# 2024-4T-MNT-3.net
KiCad netlist of a schematic drawn in EasyEDA Pro
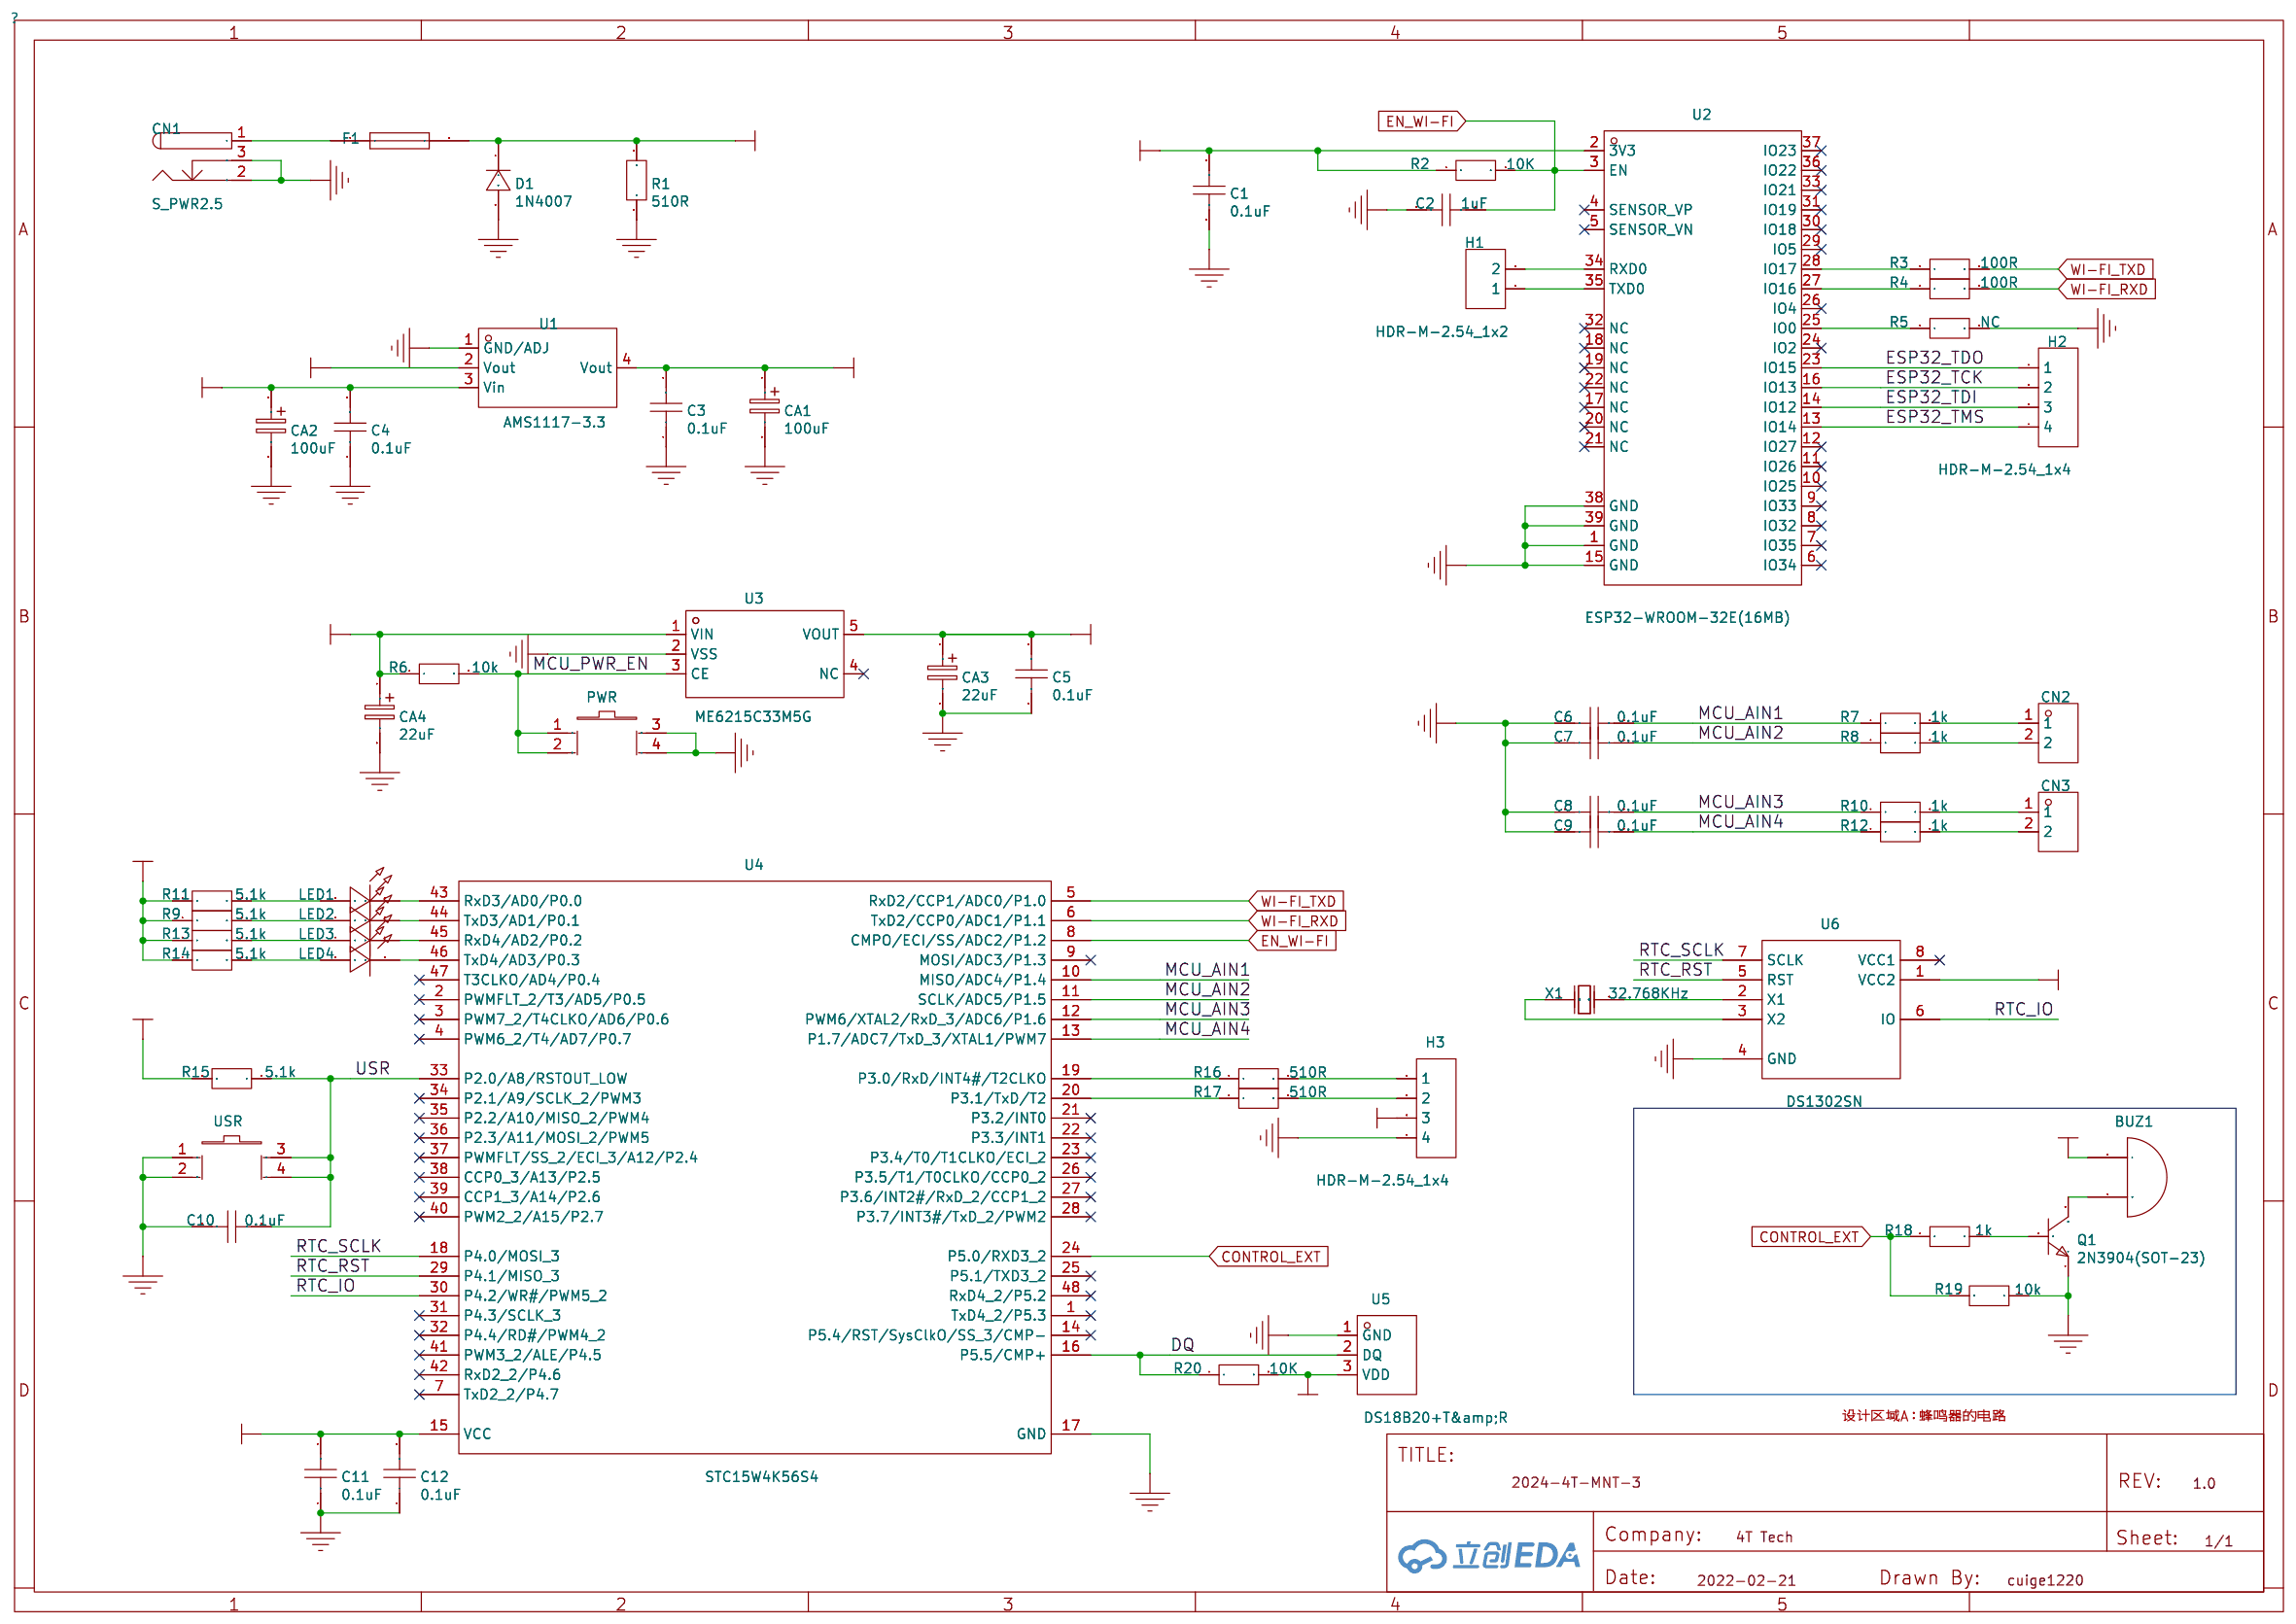
[diagram p0: schematic sheet]

(export (version "E")
  (design (tool "Eeschema 10.0.6"))
  (components
    (comp (ref "BUZ1") (value "BUZ1") (libsource (lib "easyedapro") (part "BUZ1")))
    (comp (ref "C1") (value "0.1uF") (libsource (lib "easyedapro") (part "0.1uF")))
    (comp (ref "C2") (value "1uF") (libsource (lib "easyedapro") (part "1uF")))
    (comp (ref "C3") (value "0.1uF") (libsource (lib "easyedapro") (part "0.1uF")))
    (comp (ref "C4") (value "0.1uF") (libsource (lib "easyedapro") (part "0.1uF")))
    (comp (ref "C5") (value "0.1uF") (libsource (lib "easyedapro") (part "0.1uF")))
    (comp (ref "C6") (value "0.1uF") (libsource (lib "easyedapro") (part "0.1uF")))
    (comp (ref "C7") (value "0.1uF") (libsource (lib "easyedapro") (part "0.1uF")))
    (comp (ref "C8") (value "0.1uF") (libsource (lib "easyedapro") (part "0.1uF")))
    (comp (ref "C9") (value "0.1uF") (libsource (lib "easyedapro") (part "0.1uF")))
    (comp (ref "C10") (value "0.1uF") (libsource (lib "easyedapro") (part "0.1uF")))
    (comp (ref "C11") (value "0.1uF") (libsource (lib "easyedapro") (part "0.1uF")))
    (comp (ref "C12") (value "0.1uF") (libsource (lib "easyedapro") (part "0.1uF")))
    (comp (ref "CA1") (value "100uF") (libsource (lib "easyedapro") (part "100uF")))
    (comp (ref "CA2") (value "100uF") (libsource (lib "easyedapro") (part "100uF")))
    (comp (ref "CA3") (value "22uF") (libsource (lib "easyedapro") (part "22uF")))
    (comp (ref "CA4") (value "22uF") (libsource (lib "easyedapro") (part "22uF")))
    (comp (ref "CN1") (value "S_PWR2.5") (libsource (lib "easyedapro") (part "S_PWR2.5")))
    (comp (ref "CN2")
      (value "DB128L-5.08-2P")
      (fields (field (name "Manufacturer") "DIBO"))
      (libsource (lib "easyedapro") (part "DB128L-5.08-2P"))
    )
    (comp (ref "CN3")
      (value "DB128L-5.08-2P")
      (fields (field (name "Manufacturer") "DIBO"))
      (libsource (lib "easyedapro") (part "DB128L-5.08-2P"))
    )
    (comp (ref "D1")
      (value "1N4007")
      (fields (field (name "Manufacturer") "SEMTECH"))
      (libsource (lib "easyedapro") (part "1N4007"))
    )
    (comp (ref "F1")
      (value "ASMD1210-075")
      (fields (field (name "Publisher") "Altium Limited"))
      (libsource (lib "easyedapro") (part "ASMD1210-075"))
    )
    (comp (ref "H1") (value "HDR-M-2.54_1x2") (libsource (lib "easyedapro") (part "HDR-M-2.54_1x2")))
    (comp (ref "H2") (value "HDR-M-2.54_1x4") (libsource (lib "easyedapro") (part "HDR-M-2.54_1x4")))
    (comp (ref "H3") (value "HDR-M-2.54_1x4") (libsource (lib "easyedapro") (part "HDR-M-2.54_1x4")))
    (comp (ref "LED1")
      (value "LED-TH-3mm_R")
      (fields
        (field (name "Manufacturer Part") "204-10SDRD/S530-A3-L")
        (field (name "Manufacturer") "EVERLIGHT(台湾亿光)")
      )
      (libsource (lib "easyedapro") (part "LED-TH-3mm_R"))
    )
    (comp (ref "LED2")
      (value "LED-TH-3mm_R")
      (fields
        (field (name "Manufacturer Part") "204-10SDRD/S530-A3-L")
        (field (name "Manufacturer") "EVERLIGHT(台湾亿光)")
      )
      (libsource (lib "easyedapro") (part "LED-TH-3mm_R"))
    )
    (comp (ref "LED3")
      (value "LED-TH-3mm_R")
      (fields
        (field (name "Manufacturer Part") "204-10SDRD/S530-A3-L")
        (field (name "Manufacturer") "EVERLIGHT(台湾亿光)")
      )
      (libsource (lib "easyedapro") (part "LED-TH-3mm_R"))
    )
    (comp (ref "LED4")
      (value "LED-TH-3mm_R")
      (fields
        (field (name "Manufacturer Part") "204-10SDRD/S530-A3-L")
        (field (name "Manufacturer") "EVERLIGHT(台湾亿光)")
      )
      (libsource (lib "easyedapro") (part "LED-TH-3mm_R"))
    )
    (comp (ref "PWR")
      (value "6x6x6Plastic head")
      (fields (field (name "Manufacturer") "ReliaPro"))
      (libsource (lib "easyedapro") (part "6x6x6Plastic head"))
    )
    (comp (ref "Q1")
      (value "2N3904(SOT-23)")
      (fields (field (name "Manufacturer Part") "2n3904S-RTK/PS") (field (name "Manufacturer") "KEC"))
      (libsource (lib "easyedapro") (part "2N3904(SOT-23)"))
    )
    (comp (ref "R1") (value "510R") (libsource (lib "easyedapro") (part "510R")))
    (comp (ref "R2") (value "10K") (libsource (lib "easyedapro") (part "10k")))
    (comp (ref "R3") (value "100R") (libsource (lib "easyedapro") (part "100R")))
    (comp (ref "R4") (value "100R") (libsource (lib "easyedapro") (part "100R")))
    (comp (ref "R5") (value "NC") (libsource (lib "easyedapro") (part "NC")))
    (comp (ref "R6") (value "10k") (libsource (lib "easyedapro") (part "10k")))
    (comp (ref "R7") (value "1k") (libsource (lib "easyedapro") (part "1K")))
    (comp (ref "R8") (value "1k") (libsource (lib "easyedapro") (part "1K")))
    (comp (ref "R9") (value "5.1k") (libsource (lib "easyedapro") (part "5.1k")))
    (comp (ref "R10") (value "1k") (libsource (lib "easyedapro") (part "1K")))
    (comp (ref "R11") (value "5.1k") (libsource (lib "easyedapro") (part "5.1k")))
    (comp (ref "R12") (value "1k") (libsource (lib "easyedapro") (part "1K")))
    (comp (ref "R13") (value "5.1k") (libsource (lib "easyedapro") (part "5.1k")))
    (comp (ref "R14") (value "5.1k") (libsource (lib "easyedapro") (part "5.1k")))
    (comp (ref "R15") (value "5.1k") (libsource (lib "easyedapro") (part "5.1k")))
    (comp (ref "R16") (value "510R") (libsource (lib "easyedapro") (part "510R")))
    (comp (ref "R17") (value "510R") (libsource (lib "easyedapro") (part "510R")))
    (comp (ref "R18") (value "1k") (libsource (lib "easyedapro") (part "1K")))
    (comp (ref "R19") (value "10k") (libsource (lib "easyedapro") (part "10k")))
    (comp (ref "R20") (value "10K") (libsource (lib "easyedapro") (part "10k")))
    (comp (ref "U1")
      (value "AMS1117-3.3")
      (fields (field (name "Manufacturer") "AMS"))
      (libsource (lib "easyedapro") (part "AMS1117-3.3"))
    )
    (comp (ref "U2")
      (value "ESP32-WROOM-32E(16MB)")
      (fields (field (name "Manufacturer") "Espressif Systems"))
      (libsource (lib "easyedapro") (part "ESP32-WROOM-32E(16MB)"))
    )
    (comp (ref "U3")
      (value "ME6215C33M5G")
      (fields (field (name "Manufacturer") "MICRONE"))
      (libsource (lib "easyedapro") (part "ME6215C33M5G"))
    )
    (comp (ref "U4")
      (value "STC15W4K56S4")
      (fields (field (name "Manufacturer") "STC"))
      (libsource (lib "easyedapro") (part "STC15W4K56S4"))
    )
    (comp (ref "U5")
      (value "DS18B20+T&amp;R")
      (fields (field (name "Manufacturer") "MAXIM(美信)"))
      (libsource (lib "easyedapro") (part "DS18B20+T&amp;R"))
    )
    (comp (ref "U6") (value "DS1302SN") (libsource (lib "easyedapro") (part "DS1302SN")))
    (comp (ref "USR")
      (value "6x6x6Plastic head")
      (fields (field (name "Manufacturer") "ReliaPro"))
      (libsource (lib "easyedapro") (part "6x6x6Plastic head"))
    )
    (comp (ref "X1")
      (value "32.768KHz")
      (fields (field (name "Manufacturer Part") "CFS-20632768EZFB") (field (name "Manufacturer") "CITIZEN"))
      (libsource (lib "easyedapro") (part "32.768KHz"))
    )
  )
  (nets
    (net (code "1") (name "+5V0") (class "Default")
      (node (ref "C4") (pin "2") (pinfunction "2_2") (pintype "input"))
      (node (ref "CA2") (pin "1") (pinfunction "1_1") (pintype "input"))
      (node (ref "CA4") (pin "1") (pinfunction "1_1") (pintype "input"))
      (node (ref "D1") (pin "1") (pinfunction "1_1") (pintype "input"))
      (node (ref "F1") (pin "2") (pinfunction "2_2") (pintype "input"))
      (node (ref "R1") (pin "2") (pinfunction "2_2") (pintype "input"))
      (node (ref "R6") (pin "1") (pinfunction "1_1") (pintype "input"))
      (node (ref "U1") (pin "3") (pinfunction "Vin_3") (pintype "input"))
      (node (ref "U3") (pin "1") (pinfunction "VIN_1") (pintype "input"))
    )
    (net (code "2") (name "/DQ") (class "Default")
      (node (ref "R20") (pin "1") (pinfunction "1_1") (pintype "input"))
      (node (ref "U4") (pin "16") (pinfunction "P5.5/CMP+_16") (pintype "input"))
      (node (ref "U5") (pin "2") (pinfunction "DQ_2") (pintype "input"))
    )
    (net (code "3") (name "/ESP32_TCK") (class "Default")
      (node (ref "H2") (pin "2") (pinfunction "2_2") (pintype "input"))
      (node (ref "U2") (pin "16") (pinfunction "IO13_16") (pintype "input"))
    )
    (net (code "4") (name "/ESP32_TDI") (class "Default")
      (node (ref "H2") (pin "3") (pinfunction "3_3") (pintype "input"))
      (node (ref "U2") (pin "14") (pinfunction "IO12_14") (pintype "input"))
    )
    (net (code "5") (name "/ESP32_TDO") (class "Default")
      (node (ref "H2") (pin "1") (pinfunction "1_1") (pintype "input"))
      (node (ref "U2") (pin "23") (pinfunction "IO15_23") (pintype "input"))
    )
    (net (code "6") (name "/ESP32_TMS") (class "Default")
      (node (ref "H2") (pin "4") (pinfunction "4_4") (pintype "input"))
      (node (ref "U2") (pin "13") (pinfunction "IO14_13") (pintype "input"))
    )
    (net (code "7") (name "/MCU_AIN1") (class "Default")
      (node (ref "C6") (pin "2") (pinfunction "2_2") (pintype "input"))
      (node (ref "R7") (pin "1") (pinfunction "1_1") (pintype "input"))
      (node (ref "U4") (pin "10") (pinfunction "MISO/ADC4/P1.4_10") (pintype "input"))
    )
    (net (code "8") (name "/MCU_AIN2") (class "Default")
      (node (ref "C7") (pin "2") (pinfunction "2_2") (pintype "input"))
      (node (ref "R8") (pin "1") (pinfunction "1_1") (pintype "input"))
      (node (ref "U4") (pin "11") (pinfunction "SCLK/ADC5/P1.5_11") (pintype "input"))
    )
    (net (code "9") (name "/MCU_AIN3") (class "Default")
      (node (ref "C8") (pin "2") (pinfunction "2_2") (pintype "input"))
      (node (ref "R10") (pin "1") (pinfunction "1_1") (pintype "input"))
      (node (ref "U4") (pin "12") (pinfunction "PWM6/XTAL2/RxD_3/ADC6/P1.6_12") (pintype "input"))
    )
    (net (code "10") (name "/MCU_AIN4") (class "Default")
      (node (ref "C9") (pin "2") (pinfunction "2_2") (pintype "input"))
      (node (ref "R12") (pin "1") (pinfunction "1_1") (pintype "input"))
      (node (ref "U4") (pin "13") (pinfunction "P1.7/ADC7/TxD_3/XTAL1/PWM7_13") (pintype "input"))
    )
    (net (code "11") (name "/MCU_PWR_EN") (class "Default")
      (node (ref "PWR") (pin "1") (pinfunction "1_1") (pintype "input"))
      (node (ref "PWR") (pin "2") (pinfunction "2_2") (pintype "input"))
      (node (ref "R6") (pin "2") (pinfunction "2_2") (pintype "input"))
      (node (ref "U3") (pin "3") (pinfunction "CE_3") (pintype "input"))
    )
    (net (code "12") (name "/RTC_IO") (class "Default")
      (node (ref "U4") (pin "30") (pinfunction "P4.2/WR#/PWM5_2_30") (pintype "input"))
      (node (ref "U6") (pin "6") (pinfunction "IO_6") (pintype "bidirectional"))
    )
    (net (code "13") (name "/RTC_RST") (class "Default")
      (node (ref "U4") (pin "29") (pinfunction "P4.1/MISO_3_29") (pintype "input"))
      (node (ref "U6") (pin "5") (pinfunction "RST_5") (pintype "input"))
    )
    (net (code "14") (name "/RTC_SCLK") (class "Default")
      (node (ref "U4") (pin "18") (pinfunction "P4.0/MOSI_3_18") (pintype "input"))
      (node (ref "U6") (pin "7") (pinfunction "SCLK_7") (pintype "input"))
    )
    (net (code "15") (name "/USR") (class "Default")
      (node (ref "C10") (pin "1") (pinfunction "1_1") (pintype "input"))
      (node (ref "R15") (pin "1") (pinfunction "1_1") (pintype "input"))
      (node (ref "U4") (pin "33") (pinfunction "P2.0/A8/RSTOUT_LOW_33") (pintype "input"))
      (node (ref "USR") (pin "3") (pinfunction "3_3") (pintype "input"))
      (node (ref "USR") (pin "4") (pinfunction "4_4") (pintype "input"))
    )
    (net (code "16") (name "3.3V_MCU") (class "Default")
      (node (ref "BUZ1") (pin "1") (pinfunction "A_1") (pintype "input"))
      (node (ref "C11") (pin "2") (pinfunction "2_2") (pintype "input"))
      (node (ref "C12") (pin "2") (pinfunction "2_2") (pintype "input"))
      (node (ref "C5") (pin "2") (pinfunction "2_2") (pintype "input"))
      (node (ref "CA3") (pin "1") (pinfunction "1_1") (pintype "input"))
      (node (ref "H3") (pin "3") (pinfunction "3_3") (pintype "input"))
      (node (ref "R11") (pin "1") (pinfunction "1_1") (pintype "input"))
      (node (ref "R13") (pin "1") (pinfunction "1_1") (pintype "input"))
      (node (ref "R14") (pin "1") (pinfunction "1_1") (pintype "input"))
      (node (ref "R15") (pin "2") (pinfunction "2_2") (pintype "input"))
      (node (ref "R20") (pin "2") (pinfunction "2_2") (pintype "input"))
      (node (ref "R9") (pin "1") (pinfunction "1_1") (pintype "input"))
      (node (ref "U3") (pin "5") (pinfunction "VOUT_5") (pintype "input"))
      (node (ref "U4") (pin "15") (pinfunction "VCC_15") (pintype "input"))
      (node (ref "U5") (pin "3") (pinfunction "VDD_3") (pintype "input"))
      (node (ref "U6") (pin "1") (pinfunction "VCC2_1") (pintype "input"))
    )
    (net (code "17") (name "3.3V_WIFI") (class "Default")
      (node (ref "C1") (pin "2") (pinfunction "2_2") (pintype "input"))
      (node (ref "C3") (pin "2") (pinfunction "2_2") (pintype "input"))
      (node (ref "CA1") (pin "1") (pinfunction "1_1") (pintype "input"))
      (node (ref "R2") (pin "1") (pinfunction "1_1") (pintype "input"))
      (node (ref "U1") (pin "2") (pinfunction "Vout_2") (pintype "input"))
      (node (ref "U1") (pin "4") (pinfunction "Vout_4") (pintype "input"))
      (node (ref "U2") (pin "2") (pinfunction "3V3_2") (pintype "input"))
    )
    (net (code "18") (name "CONTROL_EXT") (class "Default")
      (node (ref "R18") (pin "2") (pinfunction "2_2") (pintype "input"))
      (node (ref "R19") (pin "2") (pinfunction "2_2") (pintype "input"))
      (node (ref "U4") (pin "24") (pinfunction "P5.0/RXD3_2_24") (pintype "input"))
    )
    (net (code "19") (name "EN_WI-FI") (class "Default")
      (node (ref "C2") (pin "1") (pinfunction "1_1") (pintype "input"))
      (node (ref "R2") (pin "2") (pinfunction "2_2") (pintype "input"))
      (node (ref "U2") (pin "3") (pinfunction "EN_3") (pintype "input"))
      (node (ref "U4") (pin "8") (pinfunction "CMPO/ECI/SS/ADC2/P1.2_8") (pintype "input"))
    )
    (net (code "20") (name "GND") (class "Default")
      (node (ref "C1") (pin "1") (pinfunction "1_1") (pintype "input"))
      (node (ref "C10") (pin "2") (pinfunction "2_2") (pintype "input"))
      (node (ref "C11") (pin "1") (pinfunction "1_1") (pintype "input"))
      (node (ref "C12") (pin "1") (pinfunction "1_1") (pintype "input"))
      (node (ref "C2") (pin "2") (pinfunction "2_2") (pintype "input"))
      (node (ref "C3") (pin "1") (pinfunction "1_1") (pintype "input"))
      (node (ref "C4") (pin "1") (pinfunction "1_1") (pintype "input"))
      (node (ref "C5") (pin "1") (pinfunction "1_1") (pintype "input"))
      (node (ref "C6") (pin "1") (pinfunction "1_1") (pintype "input"))
      (node (ref "C7") (pin "1") (pinfunction "1_1") (pintype "input"))
      (node (ref "C8") (pin "1") (pinfunction "1_1") (pintype "input"))
      (node (ref "C9") (pin "1") (pinfunction "1_1") (pintype "input"))
      (node (ref "CA1") (pin "2") (pinfunction "2_2") (pintype "input"))
      (node (ref "CA2") (pin "2") (pinfunction "2_2") (pintype "input"))
      (node (ref "CA3") (pin "2") (pinfunction "2_2") (pintype "input"))
      (node (ref "CA4") (pin "2") (pinfunction "2_2") (pintype "input"))
      (node (ref "CN1") (pin "2") (pinfunction "2_2") (pintype "input"))
      (node (ref "CN1") (pin "3") (pinfunction "3_3") (pintype "input"))
      (node (ref "D1") (pin "2") (pinfunction "2_2") (pintype "input"))
      (node (ref "H3") (pin "4") (pinfunction "4_4") (pintype "input"))
      (node (ref "PWR") (pin "3") (pinfunction "3_3") (pintype "input"))
      (node (ref "PWR") (pin "4") (pinfunction "4_4") (pintype "input"))
      (node (ref "Q1") (pin "1") (pinfunction "E_1") (pintype "input"))
      (node (ref "R1") (pin "1") (pinfunction "1_1") (pintype "input"))
      (node (ref "R19") (pin "1") (pinfunction "1_1") (pintype "input"))
      (node (ref "R5") (pin "2") (pinfunction "2_2") (pintype "input"))
      (node (ref "U1") (pin "1") (pinfunction "GND/ADJ_1") (pintype "input"))
      (node (ref "U2") (pin "1") (pinfunction "GND_1") (pintype "input"))
      (node (ref "U2") (pin "15") (pinfunction "GND_15") (pintype "input"))
      (node (ref "U2") (pin "38") (pinfunction "GND_38") (pintype "input"))
      (node (ref "U2") (pin "39") (pinfunction "GND_39") (pintype "input"))
      (node (ref "U3") (pin "2") (pinfunction "VSS_2") (pintype "input"))
      (node (ref "U4") (pin "17") (pinfunction "GND_17") (pintype "input"))
      (node (ref "U5") (pin "1") (pinfunction "GND_1") (pintype "input"))
      (node (ref "U6") (pin "4") (pinfunction "GND_4") (pintype "input"))
      (node (ref "USR") (pin "1") (pinfunction "1_1") (pintype "input"))
      (node (ref "USR") (pin "2") (pinfunction "2_2") (pintype "input"))
    )
    (net (code "21") (name "Net-(BUZ1-B)") (class "Default")
      (node (ref "BUZ1") (pin "2") (pinfunction "B_2") (pintype "input"))
      (node (ref "Q1") (pin "3") (pinfunction "C_3") (pintype "input"))
    )
    (net (code "22") (name "Net-(CN1-Pad1)") (class "Default")
      (node (ref "CN1") (pin "1") (pinfunction "1_1") (pintype "input"))
      (node (ref "F1") (pin "1") (pinfunction "1_1") (pintype "input"))
    )
    (net (code "23") (name "Net-(CN2-Pad1)") (class "Default")
      (node (ref "CN2") (pin "1") (pinfunction "1_1") (pintype "input"))
      (node (ref "R7") (pin "2") (pinfunction "2_2") (pintype "input"))
    )
    (net (code "24") (name "Net-(CN2-Pad2)") (class "Default")
      (node (ref "CN2") (pin "2") (pinfunction "2_2") (pintype "input"))
      (node (ref "R8") (pin "2") (pinfunction "2_2") (pintype "input"))
    )
    (net (code "25") (name "Net-(CN3-Pad1)") (class "Default")
      (node (ref "CN3") (pin "1") (pinfunction "1_1") (pintype "input"))
      (node (ref "R10") (pin "2") (pinfunction "2_2") (pintype "input"))
    )
    (net (code "26") (name "Net-(CN3-Pad2)") (class "Default")
      (node (ref "CN3") (pin "2") (pinfunction "2_2") (pintype "input"))
      (node (ref "R12") (pin "2") (pinfunction "2_2") (pintype "input"))
    )
    (net (code "27") (name "Net-(H3-Pad1)") (class "Default")
      (node (ref "H3") (pin "1") (pinfunction "1_1") (pintype "input"))
      (node (ref "R16") (pin "2") (pinfunction "2_2") (pintype "input"))
    )
    (net (code "28") (name "Net-(H3-Pad2)") (class "Default")
      (node (ref "H3") (pin "2") (pinfunction "2_2") (pintype "input"))
      (node (ref "R17") (pin "2") (pinfunction "2_2") (pintype "input"))
    )
    (net (code "29") (name "Net-(LED1-Pad1)") (class "Default")
      (node (ref "LED1") (pin "1") (pinfunction "1_1") (pintype "input"))
      (node (ref "R9") (pin "2") (pinfunction "2_2") (pintype "input"))
    )
    (net (code "30") (name "Net-(LED2-Pad1)") (class "Default")
      (node (ref "LED2") (pin "1") (pinfunction "1_1") (pintype "input"))
      (node (ref "R11") (pin "2") (pinfunction "2_2") (pintype "input"))
    )
    (net (code "31") (name "Net-(LED3-Pad1)") (class "Default")
      (node (ref "LED3") (pin "1") (pinfunction "1_1") (pintype "input"))
      (node (ref "R13") (pin "2") (pinfunction "2_2") (pintype "input"))
    )
    (net (code "32") (name "Net-(LED4-Pad1)") (class "Default")
      (node (ref "LED4") (pin "1") (pinfunction "1_1") (pintype "input"))
      (node (ref "R14") (pin "2") (pinfunction "2_2") (pintype "input"))
    )
    (net (code "33") (name "Net-(Q1-B)") (class "Default")
      (node (ref "Q1") (pin "2") (pinfunction "B_2") (pintype "input"))
      (node (ref "R18") (pin "1") (pinfunction "1_1") (pintype "input"))
    )
    (net (code "34") (name "Net-(U2-IO0)") (class "Default")
      (node (ref "R5") (pin "1") (pinfunction "1_1") (pintype "input"))
      (node (ref "U2") (pin "25") (pinfunction "IO0_25") (pintype "input"))
    )
    (net (code "35") (name "Net-(U2-IO16)") (class "Default")
      (node (ref "R4") (pin "1") (pinfunction "1_1") (pintype "input"))
      (node (ref "U2") (pin "27") (pinfunction "IO16_27") (pintype "input"))
    )
    (net (code "36") (name "Net-(U2-IO17)") (class "Default")
      (node (ref "R3") (pin "1") (pinfunction "1_1") (pintype "input"))
      (node (ref "U2") (pin "28") (pinfunction "IO17_28") (pintype "input"))
    )
    (net (code "37") (name "Net-(U2-RXD0)") (class "Default")
      (node (ref "H1") (pin "2") (pinfunction "2_2") (pintype "input"))
      (node (ref "U2") (pin "34") (pinfunction "RXD0_34") (pintype "input"))
    )
    (net (code "38") (name "Net-(U2-TXD0)") (class "Default")
      (node (ref "H1") (pin "1") (pinfunction "1_1") (pintype "input"))
      (node (ref "U2") (pin "35") (pinfunction "TXD0_35") (pintype "input"))
    )
    (net (code "39") (name "Net-(U4-P3.0{slash}RxD{slash}INT4#{slash}T2CLKO)") (class "Default")
      (node (ref "R16") (pin "1") (pinfunction "1_1") (pintype "input"))
      (node (ref "U4") (pin "19") (pinfunction "P3.0/RxD/INT4#/T2CLKO_19") (pintype "input"))
    )
    (net (code "40") (name "Net-(U4-P3.1{slash}TxD{slash}T2)") (class "Default")
      (node (ref "R17") (pin "1") (pinfunction "1_1") (pintype "input"))
      (node (ref "U4") (pin "20") (pinfunction "P3.1/TxD/T2_20") (pintype "input"))
    )
    (net (code "41") (name "Net-(U4-RxD3{slash}AD0{slash}P0.0)") (class "Default")
      (node (ref "LED1") (pin "2") (pinfunction "2_2") (pintype "input"))
      (node (ref "U4") (pin "43") (pinfunction "RxD3/AD0/P0.0_43") (pintype "input"))
    )
    (net (code "42") (name "Net-(U4-RxD4{slash}AD2{slash}P0.2)") (class "Default")
      (node (ref "LED3") (pin "2") (pinfunction "2_2") (pintype "input"))
      (node (ref "U4") (pin "45") (pinfunction "RxD4/AD2/P0.2_45") (pintype "input"))
    )
    (net (code "43") (name "Net-(U4-TxD3{slash}AD1{slash}P0.1)") (class "Default")
      (node (ref "LED2") (pin "2") (pinfunction "2_2") (pintype "input"))
      (node (ref "U4") (pin "44") (pinfunction "TxD3/AD1/P0.1_44") (pintype "input"))
    )
    (net (code "44") (name "Net-(U4-TxD4{slash}AD3{slash}P0.3)") (class "Default")
      (node (ref "LED4") (pin "2") (pinfunction "2_2") (pintype "input"))
      (node (ref "U4") (pin "46") (pinfunction "TxD4/AD3/P0.3_46") (pintype "input"))
    )
    (net (code "45") (name "Net-(U6-X1)") (class "Default")
      (node (ref "U6") (pin "2") (pinfunction "X1_2") (pintype "input"))
      (node (ref "X1") (pin "2") (pinfunction "OSC2_2") (pintype "input"))
    )
    (net (code "46") (name "Net-(U6-X2)") (class "Default")
      (node (ref "U6") (pin "3") (pinfunction "X2_3") (pintype "input"))
      (node (ref "X1") (pin "1") (pinfunction "OSC1_1") (pintype "input"))
    )
    (net (code "47") (name "WI-FI_RXD") (class "Default")
      (node (ref "R4") (pin "2") (pinfunction "2_2") (pintype "input"))
      (node (ref "U4") (pin "6") (pinfunction "TxD2/CCP0/ADC1/P1.1_6") (pintype "input"))
    )
    (net (code "48") (name "WI-FI_TXD") (class "Default")
      (node (ref "R3") (pin "2") (pinfunction "2_2") (pintype "input"))
      (node (ref "U4") (pin "5") (pinfunction "RxD2/CCP1/ADC0/P1.0_5") (pintype "input"))
    )
    (net (code "49") (name "unconnected-(U2-IO2-Pad24)") (class "Default")
      (node (ref "U2") (pin "24") (pinfunction "IO2_24") (pintype "input+no_connect"))
    )
    (net (code "50") (name "unconnected-(U2-IO4-Pad26)") (class "Default")
      (node (ref "U2") (pin "26") (pinfunction "IO4_26") (pintype "input+no_connect"))
    )
    (net (code "51") (name "unconnected-(U2-IO5-Pad29)") (class "Default")
      (node (ref "U2") (pin "29") (pinfunction "IO5_29") (pintype "input+no_connect"))
    )
    (net (code "52") (name "unconnected-(U2-IO18-Pad30)") (class "Default")
      (node (ref "U2") (pin "30") (pinfunction "IO18_30") (pintype "input+no_connect"))
    )
    (net (code "53") (name "unconnected-(U2-IO19-Pad31)") (class "Default")
      (node (ref "U2") (pin "31") (pinfunction "IO19_31") (pintype "input+no_connect"))
    )
    (net (code "54") (name "unconnected-(U2-IO21-Pad33)") (class "Default")
      (node (ref "U2") (pin "33") (pinfunction "IO21_33") (pintype "input+no_connect"))
    )
    (net (code "55") (name "unconnected-(U2-IO22-Pad36)") (class "Default")
      (node (ref "U2") (pin "36") (pinfunction "IO22_36") (pintype "input+no_connect"))
    )
    (net (code "56") (name "unconnected-(U2-IO23-Pad37)") (class "Default")
      (node (ref "U2") (pin "37") (pinfunction "IO23_37") (pintype "input+no_connect"))
    )
    (net (code "57") (name "unconnected-(U2-IO25-Pad10)") (class "Default")
      (node (ref "U2") (pin "10") (pinfunction "IO25_10") (pintype "input+no_connect"))
    )
    (net (code "58") (name "unconnected-(U2-IO26-Pad11)") (class "Default")
      (node (ref "U2") (pin "11") (pinfunction "IO26_11") (pintype "input+no_connect"))
    )
    (net (code "59") (name "unconnected-(U2-IO27-Pad12)") (class "Default")
      (node (ref "U2") (pin "12") (pinfunction "IO27_12") (pintype "input+no_connect"))
    )
    (net (code "60") (name "unconnected-(U2-IO32-Pad8)") (class "Default")
      (node (ref "U2") (pin "8") (pinfunction "IO32_8") (pintype "input+no_connect"))
    )
    (net (code "61") (name "unconnected-(U2-IO33-Pad9)") (class "Default")
      (node (ref "U2") (pin "9") (pinfunction "IO33_9") (pintype "input+no_connect"))
    )
    (net (code "62") (name "unconnected-(U2-IO34-Pad6)") (class "Default")
      (node (ref "U2") (pin "6") (pinfunction "IO34_6") (pintype "input+no_connect"))
    )
    (net (code "63") (name "unconnected-(U2-IO35-Pad7)") (class "Default")
      (node (ref "U2") (pin "7") (pinfunction "IO35_7") (pintype "input+no_connect"))
    )
    (net (code "64") (name "unconnected-(U2-NC-Pad17)") (class "Default")
      (node (ref "U2") (pin "17") (pinfunction "NC_17") (pintype "input+no_connect"))
    )
    (net (code "65") (name "unconnected-(U2-NC-Pad18)") (class "Default")
      (node (ref "U2") (pin "18") (pinfunction "NC_18") (pintype "input+no_connect"))
    )
    (net (code "66") (name "unconnected-(U2-NC-Pad19)") (class "Default")
      (node (ref "U2") (pin "19") (pinfunction "NC_19") (pintype "input+no_connect"))
    )
    (net (code "67") (name "unconnected-(U2-NC-Pad20)") (class "Default")
      (node (ref "U2") (pin "20") (pinfunction "NC_20") (pintype "input+no_connect"))
    )
    (net (code "68") (name "unconnected-(U2-NC-Pad21)") (class "Default")
      (node (ref "U2") (pin "21") (pinfunction "NC_21") (pintype "input+no_connect"))
    )
    (net (code "69") (name "unconnected-(U2-NC-Pad22)") (class "Default")
      (node (ref "U2") (pin "22") (pinfunction "NC_22") (pintype "input+no_connect"))
    )
    (net (code "70") (name "unconnected-(U2-NC-Pad32)") (class "Default")
      (node (ref "U2") (pin "32") (pinfunction "NC_32") (pintype "input+no_connect"))
    )
    (net (code "71") (name "unconnected-(U2-SENSOR_VN-Pad5)") (class "Default")
      (node (ref "U2") (pin "5") (pinfunction "SENSOR_VN_5") (pintype "input+no_connect"))
    )
    (net (code "72") (name "unconnected-(U2-SENSOR_VP-Pad4)") (class "Default")
      (node (ref "U2") (pin "4") (pinfunction "SENSOR_VP_4") (pintype "input+no_connect"))
    )
    (net (code "73") (name "unconnected-(U3-NC-Pad4)") (class "Default")
      (node (ref "U3") (pin "4") (pinfunction "NC_4") (pintype "input+no_connect"))
    )
    (net (code "74") (name "unconnected-(U4-CCP0_3{slash}A13{slash}P2.5-Pad38)") (class "Default")
      (node (ref "U4") (pin "38") (pinfunction "CCP0_3/A13/P2.5_38") (pintype "input+no_connect"))
    )
    (net (code "75") (name "unconnected-(U4-CCP1_3{slash}A14{slash}P2.6-Pad39)") (class "Default")
      (node (ref "U4") (pin "39") (pinfunction "CCP1_3/A14/P2.6_39") (pintype "input+no_connect"))
    )
    (net (code "76") (name "unconnected-(U4-MOSI{slash}ADC3{slash}P1.3-Pad9)") (class "Default")
      (node (ref "U4") (pin "9") (pinfunction "MOSI/ADC3/P1.3_9") (pintype "input+no_connect"))
    )
    (net (code "77") (name "unconnected-(U4-P2.1{slash}A9{slash}SCLK_2{slash}PWM3-Pad34)") (class "Default")
      (node (ref "U4") (pin "34") (pinfunction "P2.1/A9/SCLK_2/PWM3_34") (pintype "input+no_connect"))
    )
    (net (code "78") (name "unconnected-(U4-P2.2{slash}A10{slash}MISO_2{slash}PWM4-Pad35)") (class "Default")
      (node (ref "U4") (pin "35") (pinfunction "P2.2/A10/MISO_2/PWM4_35") (pintype "input+no_connect"))
    )
    (net (code "79") (name "unconnected-(U4-P2.3{slash}A11{slash}MOSI_2{slash}PWM5-Pad36)") (class "Default")
      (node (ref "U4") (pin "36") (pinfunction "P2.3/A11/MOSI_2/PWM5_36") (pintype "input+no_connect"))
    )
    (net (code "80") (name "unconnected-(U4-P3.2{slash}INT0-Pad21)") (class "Default")
      (node (ref "U4") (pin "21") (pinfunction "P3.2/INT0_21") (pintype "input+no_connect"))
    )
    (net (code "81") (name "unconnected-(U4-P3.3{slash}INT1-Pad22)") (class "Default")
      (node (ref "U4") (pin "22") (pinfunction "P3.3/INT1_22") (pintype "input+no_connect"))
    )
    (net (code "82") (name "unconnected-(U4-P3.4{slash}T0{slash}T1CLKO{slash}ECI_2-Pad23)") (class "Default")
      (node (ref "U4") (pin "23") (pinfunction "P3.4/T0/T1CLKO/ECI_2_23") (pintype "input+no_connect"))
    )
    (net (code "83") (name "unconnected-(U4-P3.5{slash}T1{slash}T0CLKO{slash}CCP0_2-Pad26)") (class "Default")
      (node (ref "U4") (pin "26") (pinfunction "P3.5/T1/T0CLKO/CCP0_2_26") (pintype "input+no_connect"))
    )
    (net (code "84") (name "unconnected-(U4-P3.6{slash}INT2#{slash}RxD_2{slash}CCP1_2-Pad27)") (class "Default")
      (node (ref "U4") (pin "27") (pinfunction "P3.6/INT2#/RxD_2/CCP1_2_27") (pintype "input+no_connect"))
    )
    (net (code "85") (name "unconnected-(U4-P3.7{slash}INT3#{slash}TxD_2{slash}PWM2-Pad28)") (class "Default")
      (node (ref "U4") (pin "28") (pinfunction "P3.7/INT3#/TxD_2/PWM2_28") (pintype "input+no_connect"))
    )
    (net (code "86") (name "unconnected-(U4-P4.3{slash}SCLK_3-Pad31)") (class "Default")
      (node (ref "U4") (pin "31") (pinfunction "P4.3/SCLK_3_31") (pintype "input+no_connect"))
    )
    (net (code "87") (name "unconnected-(U4-P4.4{slash}RD#{slash}PWM4_2-Pad32)") (class "Default")
      (node (ref "U4") (pin "32") (pinfunction "P4.4/RD#/PWM4_2_32") (pintype "input+no_connect"))
    )
    (net (code "88") (name "unconnected-(U4-P5.1{slash}TXD3_2-Pad25)") (class "Default")
      (node (ref "U4") (pin "25") (pinfunction "P5.1/TXD3_2_25") (pintype "input+no_connect"))
    )
    (net (code "89") (name "unconnected-(U4-P5.4{slash}RST{slash}SysClkO{slash}SS_3{slash}CMP--Pad14)") (class "Default")
      (node (ref "U4") (pin "14") (pinfunction "P5.4/RST/SysClkO/SS_3/CMP-_14") (pintype "input+no_connect"))
    )
    (net (code "90") (name "unconnected-(U4-PWM2_2{slash}A15{slash}P2.7-Pad40)") (class "Default")
      (node (ref "U4") (pin "40") (pinfunction "PWM2_2/A15/P2.7_40") (pintype "input+no_connect"))
    )
    (net (code "91") (name "unconnected-(U4-PWM3_2{slash}ALE{slash}P4.5-Pad41)") (class "Default")
      (node (ref "U4") (pin "41") (pinfunction "PWM3_2/ALE/P4.5_41") (pintype "input+no_connect"))
    )
    (net (code "92") (name "unconnected-(U4-PWM6_2{slash}T4{slash}AD7{slash}P0.7-Pad4)") (class "Default")
      (node (ref "U4") (pin "4") (pinfunction "PWM6_2/T4/AD7/P0.7_4") (pintype "input+no_connect"))
    )
    (net (code "93") (name "unconnected-(U4-PWM7_2{slash}T4CLKO{slash}AD6{slash}P0.6-Pad3)") (class "Default")
      (node (ref "U4") (pin "3") (pinfunction "PWM7_2/T4CLKO/AD6/P0.6_3") (pintype "input+no_connect"))
    )
    (net (code "94") (name "unconnected-(U4-PWMFLT_2{slash}T3{slash}AD5{slash}P0.5-Pad2)") (class "Default")
      (node (ref "U4") (pin "2") (pinfunction "PWMFLT_2/T3/AD5/P0.5_2") (pintype "input+no_connect"))
    )
    (net (code "95") (name "unconnected-(U4-PWMFLT{slash}SS_2{slash}ECI_3{slash}A12{slash}P2.4-Pad37)") (class "Default")
      (node (ref "U4") (pin "37") (pinfunction "PWMFLT/SS_2/ECI_3/A12/P2.4_37") (pintype "input+no_connect"))
    )
    (net (code "96") (name "unconnected-(U4-RxD2_2{slash}P4.6-Pad42)") (class "Default")
      (node (ref "U4") (pin "42") (pinfunction "RxD2_2/P4.6_42") (pintype "input+no_connect"))
    )
    (net (code "97") (name "unconnected-(U4-RxD4_2{slash}P5.2-Pad48)") (class "Default")
      (node (ref "U4") (pin "48") (pinfunction "RxD4_2/P5.2_48") (pintype "input+no_connect"))
    )
    (net (code "98") (name "unconnected-(U4-T3CLKO{slash}AD4{slash}P0.4-Pad47)") (class "Default")
      (node (ref "U4") (pin "47") (pinfunction "T3CLKO/AD4/P0.4_47") (pintype "input+no_connect"))
    )
    (net (code "99") (name "unconnected-(U4-TxD2_2{slash}P4.7-Pad7)") (class "Default")
      (node (ref "U4") (pin "7") (pinfunction "TxD2_2/P4.7_7") (pintype "input+no_connect"))
    )
    (net (code "100") (name "unconnected-(U4-TxD4_2{slash}P5.3-Pad1)") (class "Default")
      (node (ref "U4") (pin "1") (pinfunction "TxD4_2/P5.3_1") (pintype "input+no_connect"))
    )
    (net (code "101") (name "unconnected-(U6-VCC1-Pad8)") (class "Default")
      (node (ref "U6") (pin "8") (pinfunction "VCC1_8") (pintype "input+no_connect"))
    )
  )
)
